# Shuttler_AFE.net
KiCad netlist of a schematic drawn in Altium Designer
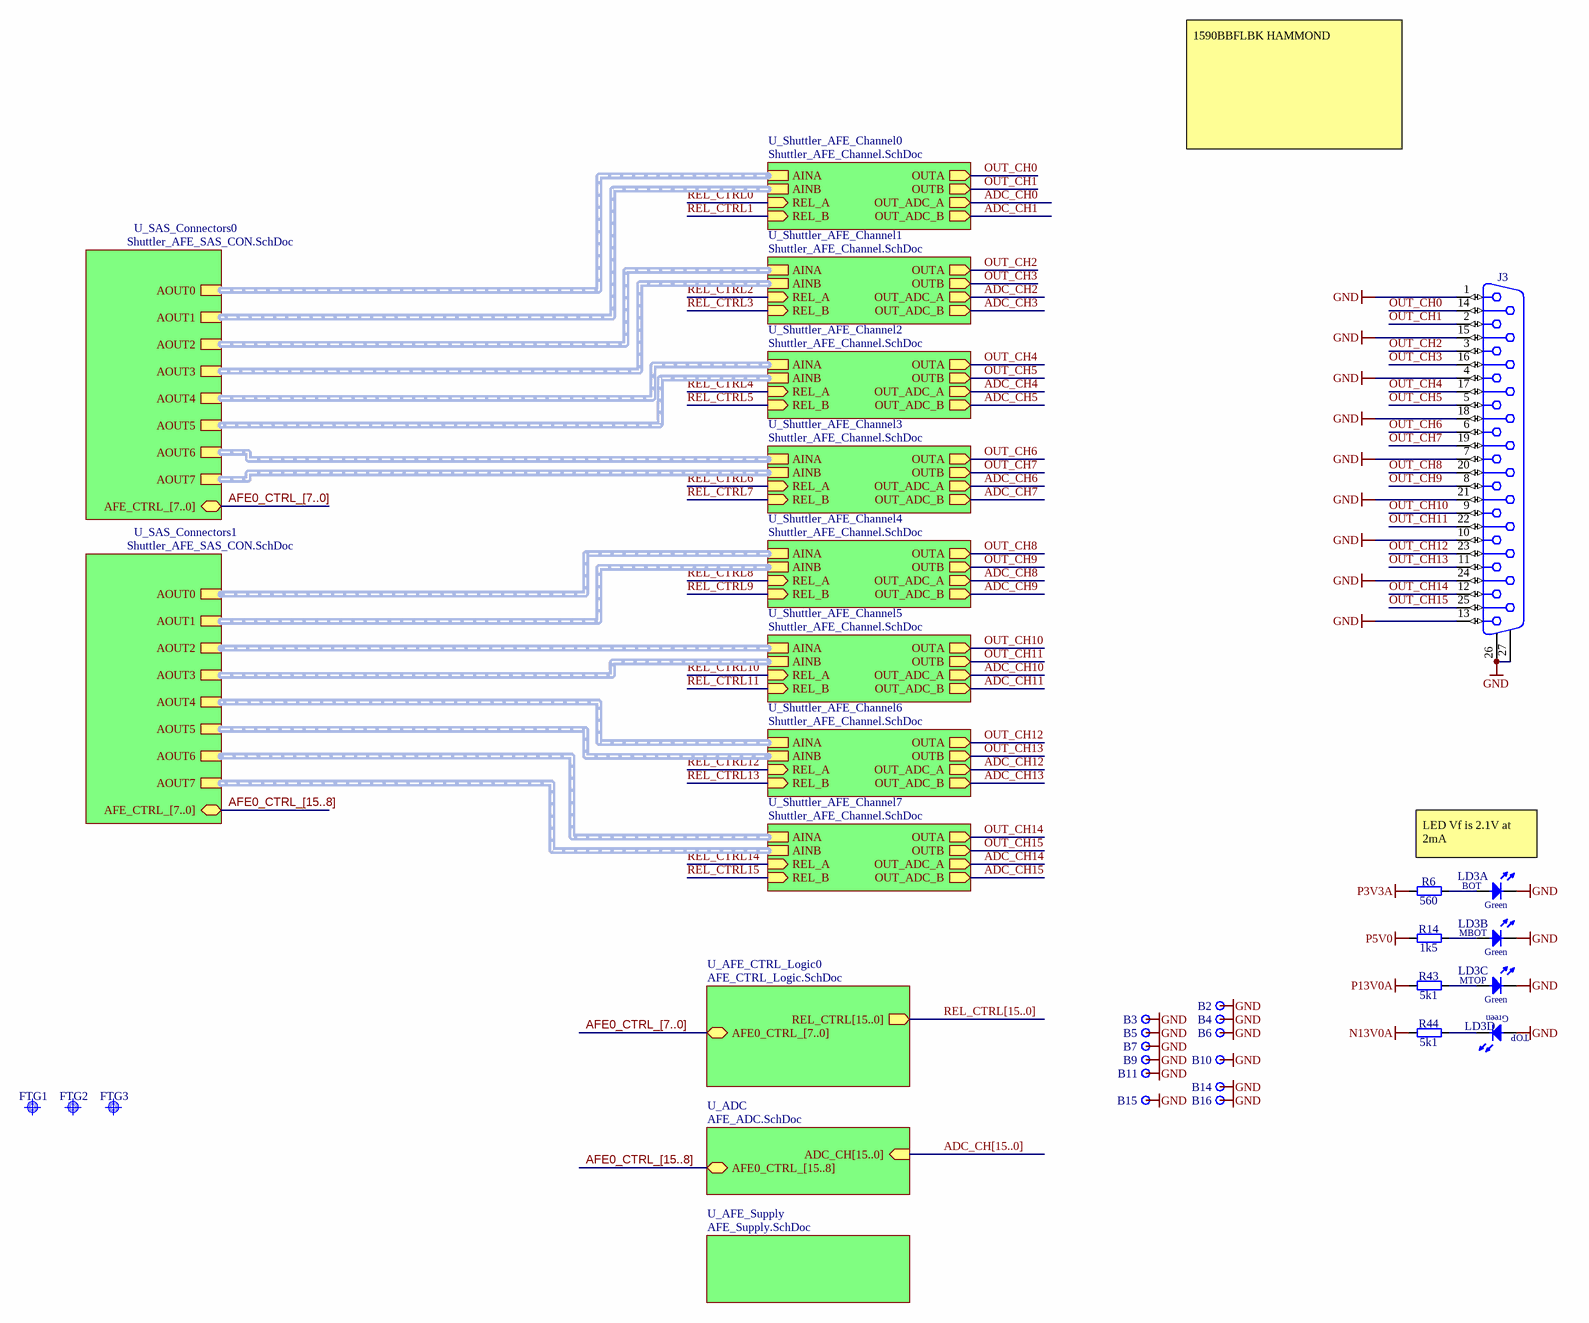
[diagram p0: Shuttler_AFE.SchDoc]

(export (version "E")
  (design (tool "Eeschema 10.0.6"))
  (components
    (comp (ref "B2")
      (value "Plated Hole")
      (footprint "MTG270_500")
      (description "Single Terminal Socket")
      (fields (field (name "PART NUMBER") "PLATED_HOLE2.7_PAD5.0") (field (name "AUTHOR") "CERN DEM JMW"))
      (libsource (lib "Eletro-mechanical") (part "Single Terminal Socket"))
    )
    (comp (ref "B3")
      (value "Plated Hole")
      (footprint "MTG270_500")
      (description "Single Terminal Socket")
      (fields (field (name "PART NUMBER") "PLATED_HOLE2.7_PAD5.0") (field (name "AUTHOR") "CERN DEM JMW"))
      (libsource (lib "Eletro-mechanical") (part "Single Terminal Socket"))
    )
    (comp (ref "B4")
      (value "Plated Hole")
      (footprint "MTG270_500")
      (description "Single Terminal Socket")
      (fields (field (name "PART NUMBER") "PLATED_HOLE2.7_PAD5.0") (field (name "AUTHOR") "CERN DEM JMW"))
      (libsource (lib "Eletro-mechanical") (part "Single Terminal Socket"))
    )
    (comp (ref "B5")
      (value "Plated Hole")
      (footprint "MTG270_500")
      (description "Single Terminal Socket")
      (fields (field (name "PART NUMBER") "PLATED_HOLE2.7_PAD5.0") (field (name "AUTHOR") "CERN DEM JMW"))
      (libsource (lib "Eletro-mechanical") (part "Single Terminal Socket"))
    )
    (comp (ref "B6")
      (value "Plated Hole")
      (footprint "MTG270_500")
      (description "Single Terminal Socket")
      (fields (field (name "PART NUMBER") "PLATED_HOLE2.7_PAD5.0") (field (name "AUTHOR") "CERN DEM JMW"))
      (libsource (lib "Eletro-mechanical") (part "Single Terminal Socket"))
    )
    (comp (ref "B7")
      (value "Plated Hole")
      (footprint "MTG270_500")
      (description "Single Terminal Socket")
      (fields (field (name "PART NUMBER") "PLATED_HOLE2.7_PAD5.0") (field (name "AUTHOR") "CERN DEM JMW"))
      (libsource (lib "Eletro-mechanical") (part "Single Terminal Socket"))
    )
    (comp (ref "B9")
      (value "Plated Hole")
      (footprint "MTG270_500")
      (description "Single Terminal Socket")
      (fields (field (name "PART NUMBER") "PLATED_HOLE2.7_PAD5.0") (field (name "AUTHOR") "CERN DEM JMW"))
      (libsource (lib "Eletro-mechanical") (part "Single Terminal Socket"))
    )
    (comp (ref "B10")
      (value "Plated Hole")
      (footprint "MTG270_500")
      (description "Single Terminal Socket")
      (fields (field (name "PART NUMBER") "PLATED_HOLE2.7_PAD5.0") (field (name "AUTHOR") "CERN DEM JMW"))
      (libsource (lib "Eletro-mechanical") (part "Single Terminal Socket"))
    )
    (comp (ref "B11")
      (value "Plated Hole")
      (footprint "MTG270_500")
      (description "Single Terminal Socket")
      (fields (field (name "PART NUMBER") "PLATED_HOLE2.7_PAD5.0") (field (name "AUTHOR") "CERN DEM JMW"))
      (libsource (lib "Eletro-mechanical") (part "Single Terminal Socket"))
    )
    (comp (ref "B14")
      (value "Plated Hole")
      (footprint "MTG270_500")
      (description "Single Terminal Socket")
      (fields (field (name "PART NUMBER") "PLATED_HOLE2.7_PAD5.0") (field (name "AUTHOR") "CERN DEM JMW"))
      (libsource (lib "Eletro-mechanical") (part "Single Terminal Socket"))
    )
    (comp (ref "B15")
      (value "Plated Hole")
      (footprint "MTG270_500")
      (description "Single Terminal Socket")
      (fields (field (name "PART NUMBER") "PLATED_HOLE2.7_PAD5.0") (field (name "AUTHOR") "CERN DEM JMW"))
      (libsource (lib "Eletro-mechanical") (part "Single Terminal Socket"))
    )
    (comp (ref "B16")
      (value "Plated Hole")
      (footprint "MTG270_500")
      (description "Single Terminal Socket")
      (fields (field (name "PART NUMBER") "PLATED_HOLE2.7_PAD5.0") (field (name "AUTHOR") "CERN DEM JMW"))
      (libsource (lib "Eletro-mechanical") (part "Single Terminal Socket"))
    )
    (comp (ref "FTG1")
      (value "Use only in PCB")
      (footprint "FIDUCIAL_TOP_S100-200")
      (description "Fiducial Target")
      (fields (field (name "PART NUMBER") "FIDUCIAL_TARGET_S100-200") (field (name "AUTHOR") "CERN DEM JLC"))
      (libsource (lib "Eletro-mechanical") (part "Fiducial Target"))
    )
    (comp (ref "FTG2")
      (value "Use only in PCB")
      (footprint "FIDUCIAL_TOP_S100-200")
      (description "Fiducial Target")
      (fields (field (name "PART NUMBER") "FIDUCIAL_TARGET_S100-200") (field (name "AUTHOR") "CERN DEM JLC"))
      (libsource (lib "Eletro-mechanical") (part "Fiducial Target"))
    )
    (comp (ref "FTG3")
      (value "Use only in PCB")
      (footprint "FIDUCIAL_TOP_S100-200")
      (description "Fiducial Target")
      (fields (field (name "PART NUMBER") "FIDUCIAL_TARGET_S100-200") (field (name "AUTHOR") "CERN DEM JLC"))
      (libsource (lib "Eletro-mechanical") (part "Fiducial Target"))
    )
    (comp (ref "J3")
      (value "D-Sub")
      (footprint "TYCO_3-1634586-2")
      (description "Connector D-sub 25 Female")
      (fields
        (field (name "PART NUMBER") "TYCO_3-1634586-2")
        (field (name "MANUFACTURER") "TYCO ELECTRONICS")
        (field (name "AUTHOR") "CERN DEM JLC")
      )
      (libsource (lib "Connectors") (part "Connector D-sub 25 Female"))
    )
    (comp (ref "LD3")
      (value "Green")
      (footprint "LED_BIVAR_H485CGDL")
      (description "LED x4 Green 1C2A-BOT_3C4A_5C6A_7C8A-TOP")
      (fields
        (field (name "PART NUMBER") "LED_BIVAR_H485CGDL")
        (field (name "MANUFACTURER") "BIVAR")
        (field (name "AUTHOR") "CERN DEM JLC")
      )
      (libsource (lib "ICs And Semiconductors") (part "LED x4 Green 1C2A-BOT_3C4A_5C6A_7C8A-TOP"))
    )
    (comp (ref "R6")
      (value "560")
      (footprint "RESC1608X55N")
      (description "Resistor - 1%")
      (fields
        (field (name "PART NUMBER") "R0603_560R_1%_0.1W_100PPM")
        (field (name "POWER") "0.1W")
        (field (name "AUTHOR") "CERN DEM JLC")
      )
      (libsource (lib "Resistors") (part "Resistor - 1%"))
    )
    (comp (ref "R14")
      (value "1k5")
      (footprint "RESC1608X55N")
      (description "Resistor - 1%")
      (fields
        (field (name "PART NUMBER") "R0603_1K5_1%_0.1W_100PPM")
        (field (name "POWER") "0.1W")
        (field (name "AUTHOR") "CERN DEM JLC")
      )
      (libsource (lib "Resistors") (part "Resistor - 1%"))
    )
    (comp (ref "R43")
      (value "5k1")
      (footprint "RESC1608X55N")
      (description "Resistor - 1%")
      (fields
        (field (name "PART NUMBER") "R0603_5K1_1%_0.1W_100PPM")
        (field (name "POWER") "0.1W")
        (field (name "AUTHOR") "CERN DEM JLC")
      )
      (libsource (lib "Resistors") (part "Resistor - 1%"))
    )
    (comp (ref "R44")
      (value "5k1")
      (footprint "RESC1608X55N")
      (description "Resistor - 1%")
      (fields
        (field (name "PART NUMBER") "R0603_5K1_1%_0.1W_100PPM")
        (field (name "POWER") "0.1W")
        (field (name "AUTHOR") "CERN DEM JLC")
      )
      (libsource (lib "Resistors") (part "Resistor - 1%"))
    )
  )
  (nets
    (net (code "52") (name "/OUT_CH0") (class "Default")
      (node (ref "J3") (pin "14") (pinfunction "14_14") (pintype "bidirectional"))
    )
    (net (code "53") (name "/OUT_CH1") (class "Default")
      (node (ref "J3") (pin "2") (pinfunction "2_2") (pintype "bidirectional"))
    )
    (net (code "54") (name "/OUT_CH2") (class "Default")
      (node (ref "J3") (pin "3") (pinfunction "3_3") (pintype "bidirectional"))
    )
    (net (code "55") (name "/OUT_CH3") (class "Default")
      (node (ref "J3") (pin "16") (pinfunction "16_16") (pintype "bidirectional"))
    )
    (net (code "56") (name "/OUT_CH4") (class "Default")
      (node (ref "J3") (pin "17") (pinfunction "17_17") (pintype "bidirectional"))
    )
    (net (code "57") (name "/OUT_CH5") (class "Default")
      (node (ref "J3") (pin "5") (pinfunction "5_5") (pintype "bidirectional"))
    )
    (net (code "58") (name "/OUT_CH6") (class "Default")
      (node (ref "J3") (pin "6") (pinfunction "6_6") (pintype "bidirectional"))
    )
    (net (code "59") (name "/OUT_CH7") (class "Default")
      (node (ref "J3") (pin "19") (pinfunction "19_19") (pintype "bidirectional"))
    )
    (net (code "60") (name "/OUT_CH8") (class "Default")
      (node (ref "J3") (pin "20") (pinfunction "20_20") (pintype "bidirectional"))
    )
    (net (code "61") (name "/OUT_CH9") (class "Default")
      (node (ref "J3") (pin "8") (pinfunction "8_8") (pintype "bidirectional"))
    )
    (net (code "62") (name "/OUT_CH10") (class "Default")
      (node (ref "J3") (pin "9") (pinfunction "9_9") (pintype "bidirectional"))
    )
    (net (code "63") (name "/OUT_CH11") (class "Default")
      (node (ref "J3") (pin "22") (pinfunction "22_22") (pintype "bidirectional"))
    )
    (net (code "64") (name "/OUT_CH12") (class "Default")
      (node (ref "J3") (pin "23") (pinfunction "23_23") (pintype "bidirectional"))
    )
    (net (code "65") (name "/OUT_CH13") (class "Default")
      (node (ref "J3") (pin "11") (pinfunction "11_11") (pintype "bidirectional"))
    )
    (net (code "66") (name "/OUT_CH14") (class "Default")
      (node (ref "J3") (pin "12") (pinfunction "12_12") (pintype "bidirectional"))
    )
    (net (code "67") (name "/OUT_CH15") (class "Default")
      (node (ref "J3") (pin "25") (pinfunction "25_25") (pintype "bidirectional"))
    )
    (net (code "85") (name "GND") (class "Default")
      (node (ref "B10") (pin "1") (pinfunction "1_1") (pintype "bidirectional"))
      (node (ref "B11") (pin "1") (pinfunction "1_1") (pintype "bidirectional"))
      (node (ref "B14") (pin "1") (pinfunction "1_1") (pintype "bidirectional"))
      (node (ref "B15") (pin "1") (pinfunction "1_1") (pintype "bidirectional"))
      (node (ref "B16") (pin "1") (pinfunction "1_1") (pintype "bidirectional"))
      (node (ref "B2") (pin "1") (pinfunction "1_1") (pintype "bidirectional"))
      (node (ref "B3") (pin "1") (pinfunction "1_1") (pintype "bidirectional"))
      (node (ref "B4") (pin "1") (pinfunction "1_1") (pintype "bidirectional"))
      (node (ref "B5") (pin "1") (pinfunction "1_1") (pintype "bidirectional"))
      (node (ref "B6") (pin "1") (pinfunction "1_1") (pintype "bidirectional"))
      (node (ref "B7") (pin "1") (pinfunction "1_1") (pintype "bidirectional"))
      (node (ref "B9") (pin "1") (pinfunction "1_1") (pintype "bidirectional"))
      (node (ref "J3") (pin "1") (pinfunction "1_1") (pintype "bidirectional"))
      (node (ref "J3") (pin "10") (pinfunction "10_10") (pintype "bidirectional"))
      (node (ref "J3") (pin "13") (pinfunction "13_13") (pintype "bidirectional"))
      (node (ref "J3") (pin "15") (pinfunction "15_15") (pintype "bidirectional"))
      (node (ref "J3") (pin "18") (pinfunction "18_18") (pintype "bidirectional"))
      (node (ref "J3") (pin "21") (pinfunction "21_21") (pintype "bidirectional"))
      (node (ref "J3") (pin "24") (pinfunction "24_24") (pintype "bidirectional"))
      (node (ref "J3") (pin "26") (pinfunction "26_26") (pintype "passive"))
      (node (ref "J3") (pin "27") (pinfunction "27_27") (pintype "passive"))
      (node (ref "J3") (pin "4") (pinfunction "4_4") (pintype "bidirectional"))
      (node (ref "J3") (pin "7") (pinfunction "7_7") (pintype "bidirectional"))
      (node (ref "LD3") (pin "1") (pinfunction "C_1") (pintype "passive"))
      (node (ref "LD3") (pin "3") (pinfunction "C_3") (pintype "passive"))
      (node (ref "LD3") (pin "5") (pinfunction "C_5") (pintype "passive"))
      (node (ref "LD3") (pin "8") (pinfunction "A_8") (pintype "passive"))
    )
    (net (code "86") (name "N13V0A") (class "Default")
      (node (ref "R44") (pin "1") (pinfunction "1_1") (pintype "passive"))
    )
    (net (code "87") (name "Net-(LD3A-A)") (class "Default")
      (node (ref "LD3") (pin "2") (pinfunction "A_2") (pintype "passive"))
      (node (ref "R6") (pin "2") (pinfunction "2_2") (pintype "passive"))
    )
    (net (code "88") (name "Net-(LD3B-A)") (class "Default")
      (node (ref "LD3") (pin "4") (pinfunction "A_4") (pintype "passive"))
      (node (ref "R14") (pin "2") (pinfunction "2_2") (pintype "passive"))
    )
    (net (code "89") (name "Net-(LD3C-A)") (class "Default")
      (node (ref "LD3") (pin "6") (pinfunction "A_6") (pintype "passive"))
      (node (ref "R43") (pin "2") (pinfunction "2_2") (pintype "passive"))
    )
    (net (code "90") (name "Net-(LD3D-C)") (class "Default")
      (node (ref "LD3") (pin "7") (pinfunction "C_7") (pintype "passive"))
      (node (ref "R44") (pin "2") (pinfunction "2_2") (pintype "passive"))
    )
    (net (code "91") (name "P3V3A") (class "Default")
      (node (ref "R6") (pin "1") (pinfunction "1_1") (pintype "passive"))
    )
    (net (code "92") (name "P5V0") (class "Default")
      (node (ref "R14") (pin "1") (pinfunction "1_1") (pintype "passive"))
    )
    (net (code "93") (name "P13V0A") (class "Default")
      (node (ref "R43") (pin "1") (pinfunction "1_1") (pintype "passive"))
    )
  )
)
